# Macropad_Schematic.net
KiCad netlist of a schematic drawn in EAGLE
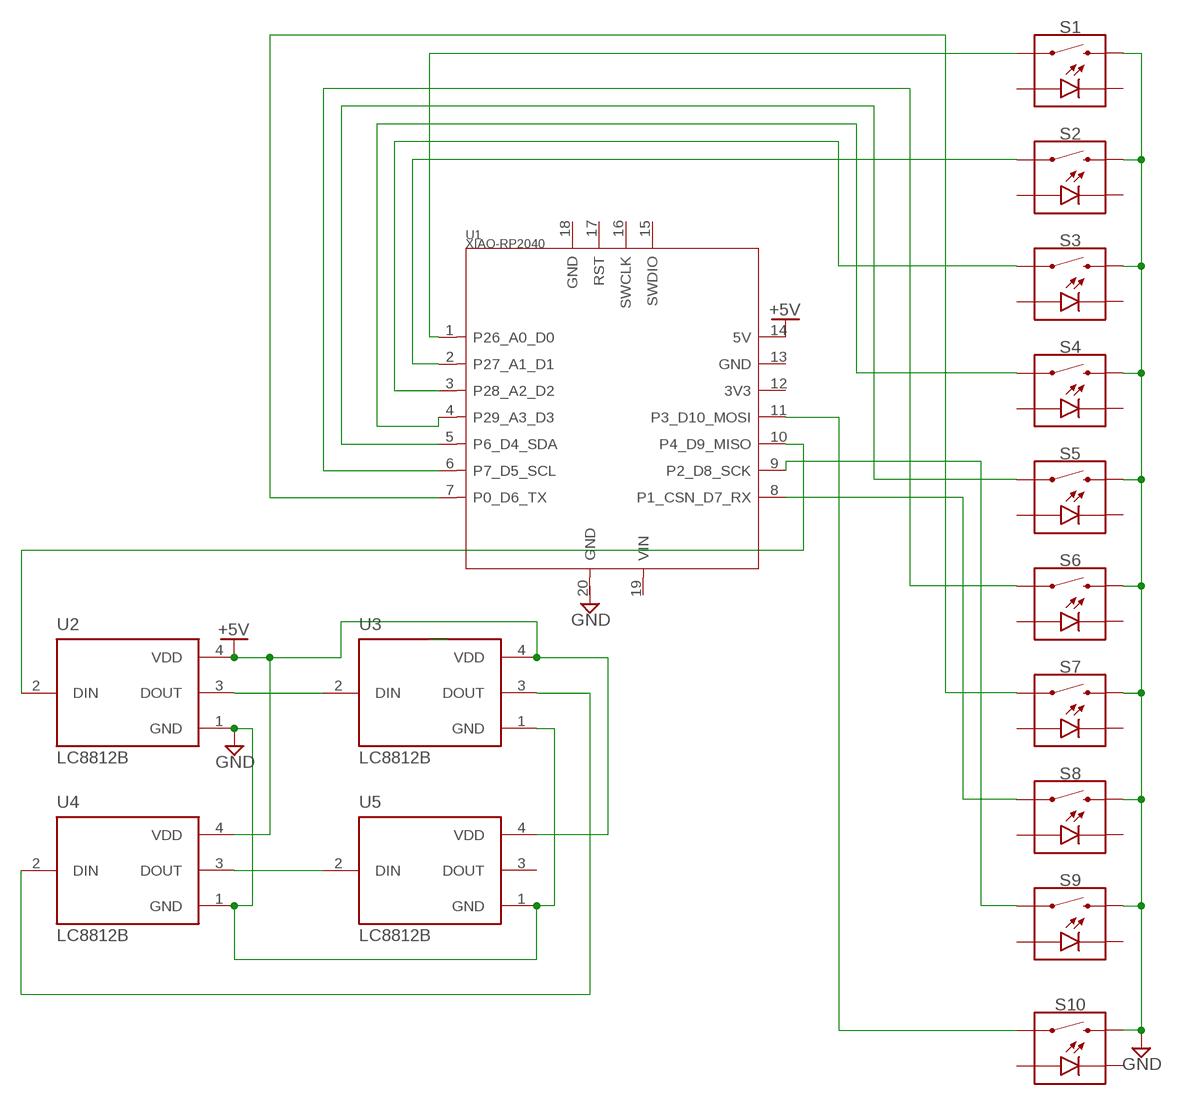
[diagram p0: schematic, sheet 1]

(export (version "E")
  (design (tool "Eeschema 10.0.6"))
  (components
    (comp (ref "S1")
      (value "MECHANICAL-KEYBOARD1U")
      (footprint "eagle-import:CHERRY-MX-LED-1U")
      (libsource (lib "eagle-import") (part "MECHANICAL-KEYBOARD1U"))
    )
    (comp (ref "S2")
      (value "MECHANICAL-KEYBOARD1U")
      (footprint "eagle-import:CHERRY-MX-LED-1U")
      (libsource (lib "eagle-import") (part "MECHANICAL-KEYBOARD1U"))
    )
    (comp (ref "S3")
      (value "MECHANICAL-KEYBOARD1U")
      (footprint "eagle-import:CHERRY-MX-LED-1U")
      (libsource (lib "eagle-import") (part "MECHANICAL-KEYBOARD1U"))
    )
    (comp (ref "S4")
      (value "MECHANICAL-KEYBOARD1U")
      (footprint "eagle-import:CHERRY-MX-LED-1U")
      (libsource (lib "eagle-import") (part "MECHANICAL-KEYBOARD1U"))
    )
    (comp (ref "S5")
      (value "MECHANICAL-KEYBOARD1U")
      (footprint "eagle-import:CHERRY-MX-LED-1U")
      (libsource (lib "eagle-import") (part "MECHANICAL-KEYBOARD1U"))
    )
    (comp (ref "S6")
      (value "MECHANICAL-KEYBOARD1U")
      (footprint "eagle-import:CHERRY-MX-LED-1U")
      (libsource (lib "eagle-import") (part "MECHANICAL-KEYBOARD1U"))
    )
    (comp (ref "S7")
      (value "MECHANICAL-KEYBOARD1U")
      (footprint "eagle-import:CHERRY-MX-LED-1U")
      (libsource (lib "eagle-import") (part "MECHANICAL-KEYBOARD1U"))
    )
    (comp (ref "S8")
      (value "MECHANICAL-KEYBOARD1U")
      (footprint "eagle-import:CHERRY-MX-LED-1U")
      (libsource (lib "eagle-import") (part "MECHANICAL-KEYBOARD1U"))
    )
    (comp (ref "S9")
      (value "MECHANICAL-KEYBOARD1U")
      (footprint "eagle-import:CHERRY-MX-LED-1U")
      (libsource (lib "eagle-import") (part "MECHANICAL-KEYBOARD1U"))
    )
    (comp (ref "S10")
      (value "MECHANICAL-KEYBOARD1U")
      (footprint "eagle-import:CHERRY-MX-LED-1U")
      (libsource (lib "eagle-import") (part "MECHANICAL-KEYBOARD1U"))
    )
    (comp (ref "U1")
      (value "XIAO-RP2040")
      (footprint "eagle-import:XIAO-SAMD21_RP2040-MODULE14P-2.54-21X17.8MM")
      (libsource (lib "eagle-import") (part "XIAO-RP2040"))
    )
    (comp (ref "U2")
      (value "LC8812B")
      (footprint "eagle-import:SOL320P540X157-4N")
      (fields (field (name "MF") "Shenzhen LED Color Optoelectronic Inc."))
      (libsource (lib "eagle-import") (part "LC8812B"))
    )
    (comp (ref "U3")
      (value "LC8812B")
      (footprint "eagle-import:SOL320P540X157-4N")
      (fields (field (name "MF") "Shenzhen LED Color Optoelectronic Inc."))
      (libsource (lib "eagle-import") (part "LC8812B"))
    )
    (comp (ref "U4")
      (value "LC8812B")
      (footprint "eagle-import:SOL320P540X157-4N")
      (fields (field (name "MF") "Shenzhen LED Color Optoelectronic Inc."))
      (libsource (lib "eagle-import") (part "LC8812B"))
    )
    (comp (ref "U5")
      (value "LC8812B")
      (footprint "eagle-import:SOL320P540X157-4N")
      (fields (field (name "MF") "Shenzhen LED Color Optoelectronic Inc."))
      (libsource (lib "eagle-import") (part "LC8812B"))
    )
  )
  (nets
    (net (code "1") (name "+5V") (class "Default")
      (node (ref "U1") (pin "14") (pinfunction "5V_14") (pintype "bidirectional"))
      (node (ref "U2") (pin "4") (pinfunction "VDD_4") (pintype "power_in"))
      (node (ref "U3") (pin "4") (pinfunction "VDD_4") (pintype "power_in"))
      (node (ref "U4") (pin "4") (pinfunction "VDD_4") (pintype "power_in"))
      (node (ref "U5") (pin "4") (pinfunction "VDD_4") (pintype "power_in"))
    )
    (net (code "2") (name "GND") (class "Default")
      (node (ref "S1") (pin "S2") (pinfunction "2_S2") (pintype "passive"))
      (node (ref "S10") (pin "S2") (pinfunction "2_S2") (pintype "passive"))
      (node (ref "S2") (pin "S2") (pinfunction "2_S2") (pintype "passive"))
      (node (ref "S3") (pin "S2") (pinfunction "2_S2") (pintype "passive"))
      (node (ref "S4") (pin "S2") (pinfunction "2_S2") (pintype "passive"))
      (node (ref "S5") (pin "S2") (pinfunction "2_S2") (pintype "passive"))
      (node (ref "S6") (pin "S2") (pinfunction "2_S2") (pintype "passive"))
      (node (ref "S7") (pin "S2") (pinfunction "2_S2") (pintype "passive"))
      (node (ref "S8") (pin "S2") (pinfunction "2_S2") (pintype "passive"))
      (node (ref "S9") (pin "S2") (pinfunction "2_S2") (pintype "passive"))
      (node (ref "U2") (pin "1") (pinfunction "GND_1") (pintype "power_in"))
      (node (ref "U3") (pin "1") (pinfunction "GND_1") (pintype "power_in"))
      (node (ref "U4") (pin "1") (pinfunction "GND_1") (pintype "power_in"))
      (node (ref "U5") (pin "1") (pinfunction "GND_1") (pintype "power_in"))
    )
    (net (code "3") (name "Net-(S1-1)") (class "Default")
      (node (ref "S1") (pin "S1") (pinfunction "1_S1") (pintype "passive"))
      (node (ref "U1") (pin "1") (pinfunction "P26_A0_D0_1") (pintype "bidirectional"))
    )
    (net (code "4") (name "Net-(S2-1)") (class "Default")
      (node (ref "S2") (pin "S1") (pinfunction "1_S1") (pintype "passive"))
      (node (ref "U1") (pin "2") (pinfunction "P27_A1_D1_2") (pintype "bidirectional"))
    )
    (net (code "5") (name "Net-(S3-1)") (class "Default")
      (node (ref "S3") (pin "S1") (pinfunction "1_S1") (pintype "passive"))
      (node (ref "U1") (pin "3") (pinfunction "P28_A2_D2_3") (pintype "bidirectional"))
    )
    (net (code "6") (name "Net-(S4-1)") (class "Default")
      (node (ref "S4") (pin "S1") (pinfunction "1_S1") (pintype "passive"))
      (node (ref "U1") (pin "4") (pinfunction "P29_A3_D3_4") (pintype "bidirectional"))
    )
    (net (code "7") (name "Net-(S5-1)") (class "Default")
      (node (ref "S5") (pin "S1") (pinfunction "1_S1") (pintype "passive"))
      (node (ref "U1") (pin "5") (pinfunction "P6_D4_SDA_5") (pintype "bidirectional"))
    )
    (net (code "8") (name "Net-(S6-1)") (class "Default")
      (node (ref "S6") (pin "S1") (pinfunction "1_S1") (pintype "passive"))
      (node (ref "U1") (pin "6") (pinfunction "P7_D5_SCL_6") (pintype "bidirectional"))
    )
    (net (code "9") (name "Net-(S7-1)") (class "Default")
      (node (ref "S7") (pin "S1") (pinfunction "1_S1") (pintype "passive"))
      (node (ref "U1") (pin "7") (pinfunction "P0_D6_TX_7") (pintype "bidirectional"))
    )
    (net (code "10") (name "Net-(S8-1)") (class "Default")
      (node (ref "S8") (pin "S1") (pinfunction "1_S1") (pintype "passive"))
      (node (ref "U1") (pin "8") (pinfunction "P1_CSN_D7_RX_8") (pintype "bidirectional"))
    )
    (net (code "11") (name "Net-(S9-1)") (class "Default")
      (node (ref "S9") (pin "S1") (pinfunction "1_S1") (pintype "passive"))
      (node (ref "U1") (pin "9") (pinfunction "P2_D8_SCK_9") (pintype "bidirectional"))
    )
    (net (code "12") (name "Net-(S10-1)") (class "Default")
      (node (ref "S10") (pin "S1") (pinfunction "1_S1") (pintype "passive"))
      (node (ref "U1") (pin "11") (pinfunction "P3_D10_MOSI_11") (pintype "bidirectional"))
    )
    (net (code "13") (name "Net-(U1-P4_D9_MISO)") (class "Default")
      (node (ref "U1") (pin "10") (pinfunction "P4_D9_MISO_10") (pintype "bidirectional"))
      (node (ref "U2") (pin "2") (pinfunction "DIN_2") (pintype "input"))
    )
    (net (code "14") (name "Net-(U2-DOUT)") (class "Default")
      (node (ref "U2") (pin "3") (pinfunction "DOUT_3") (pintype "output"))
      (node (ref "U3") (pin "2") (pinfunction "DIN_2") (pintype "input"))
    )
    (net (code "15") (name "Net-(U3-DOUT)") (class "Default")
      (node (ref "U3") (pin "3") (pinfunction "DOUT_3") (pintype "output"))
      (node (ref "U4") (pin "2") (pinfunction "DIN_2") (pintype "input"))
    )
    (net (code "16") (name "Net-(U4-DOUT)") (class "Default")
      (node (ref "U4") (pin "3") (pinfunction "DOUT_3") (pintype "output"))
      (node (ref "U5") (pin "2") (pinfunction "DIN_2") (pintype "input"))
    )
    (net (code "17") (name "unconnected-(S1-C-PadK)") (class "Default")
      (node (ref "S1") (pin "K") (pinfunction "C_K") (pintype "passive"))
    )
    (net (code "18") (name "unconnected-(S1-PadA)") (class "Default")
      (node (ref "S1") (pin "A") (pinfunction "A_A") (pintype "passive"))
    )
    (net (code "19") (name "unconnected-(S2-C-PadK)") (class "Default")
      (node (ref "S2") (pin "K") (pinfunction "C_K") (pintype "passive"))
    )
    (net (code "20") (name "unconnected-(S2-PadA)") (class "Default")
      (node (ref "S2") (pin "A") (pinfunction "A_A") (pintype "passive"))
    )
    (net (code "21") (name "unconnected-(S3-C-PadK)") (class "Default")
      (node (ref "S3") (pin "K") (pinfunction "C_K") (pintype "passive"))
    )
    (net (code "22") (name "unconnected-(S3-PadA)") (class "Default")
      (node (ref "S3") (pin "A") (pinfunction "A_A") (pintype "passive"))
    )
    (net (code "23") (name "unconnected-(S4-C-PadK)") (class "Default")
      (node (ref "S4") (pin "K") (pinfunction "C_K") (pintype "passive"))
    )
    (net (code "24") (name "unconnected-(S4-PadA)") (class "Default")
      (node (ref "S4") (pin "A") (pinfunction "A_A") (pintype "passive"))
    )
    (net (code "25") (name "unconnected-(S5-C-PadK)") (class "Default")
      (node (ref "S5") (pin "K") (pinfunction "C_K") (pintype "passive"))
    )
    (net (code "26") (name "unconnected-(S5-PadA)") (class "Default")
      (node (ref "S5") (pin "A") (pinfunction "A_A") (pintype "passive"))
    )
    (net (code "27") (name "unconnected-(S6-C-PadK)") (class "Default")
      (node (ref "S6") (pin "K") (pinfunction "C_K") (pintype "passive"))
    )
    (net (code "28") (name "unconnected-(S6-PadA)") (class "Default")
      (node (ref "S6") (pin "A") (pinfunction "A_A") (pintype "passive"))
    )
    (net (code "29") (name "unconnected-(S7-C-PadK)") (class "Default")
      (node (ref "S7") (pin "K") (pinfunction "C_K") (pintype "passive"))
    )
    (net (code "30") (name "unconnected-(S7-PadA)") (class "Default")
      (node (ref "S7") (pin "A") (pinfunction "A_A") (pintype "passive"))
    )
    (net (code "31") (name "unconnected-(S8-C-PadK)") (class "Default")
      (node (ref "S8") (pin "K") (pinfunction "C_K") (pintype "passive"))
    )
    (net (code "32") (name "unconnected-(S8-PadA)") (class "Default")
      (node (ref "S8") (pin "A") (pinfunction "A_A") (pintype "passive"))
    )
    (net (code "33") (name "unconnected-(S9-C-PadK)") (class "Default")
      (node (ref "S9") (pin "K") (pinfunction "C_K") (pintype "passive"))
    )
    (net (code "34") (name "unconnected-(S9-PadA)") (class "Default")
      (node (ref "S9") (pin "A") (pinfunction "A_A") (pintype "passive"))
    )
    (net (code "35") (name "unconnected-(S10-C-PadK)") (class "Default")
      (node (ref "S10") (pin "K") (pinfunction "C_K") (pintype "passive"))
    )
    (net (code "36") (name "unconnected-(S10-PadA)") (class "Default")
      (node (ref "S10") (pin "A") (pinfunction "A_A") (pintype "passive"))
    )
    (net (code "37") (name "unconnected-(U1-3V3-Pad12)") (class "Default")
      (node (ref "U1") (pin "12") (pinfunction "3V3_12") (pintype "bidirectional"))
    )
    (net (code "38") (name "unconnected-(U1-GND-Pad13)") (class "Default")
      (node (ref "U1") (pin "13") (pinfunction "GND_13") (pintype "bidirectional"))
    )
    (net (code "39") (name "unconnected-(U1-GND-Pad18)") (class "Default")
      (node (ref "U1") (pin "18") (pinfunction "GND_18") (pintype "bidirectional"))
    )
    (net (code "40") (name "unconnected-(U1-GND-Pad20)") (class "Default")
      (node (ref "U1") (pin "20") (pinfunction "GND_20") (pintype "bidirectional"))
    )
    (net (code "41") (name "unconnected-(U1-RST-Pad17)") (class "Default")
      (node (ref "U1") (pin "17") (pinfunction "RST_17") (pintype "bidirectional"))
    )
    (net (code "42") (name "unconnected-(U1-SWCLK-Pad16)") (class "Default")
      (node (ref "U1") (pin "16") (pinfunction "SWCLK_16") (pintype "bidirectional"))
    )
    (net (code "43") (name "unconnected-(U1-SWDIO-Pad15)") (class "Default")
      (node (ref "U1") (pin "15") (pinfunction "SWDIO_15") (pintype "bidirectional"))
    )
    (net (code "44") (name "unconnected-(U1-VIN-Pad19)") (class "Default")
      (node (ref "U1") (pin "19") (pinfunction "VIN_19") (pintype "bidirectional"))
    )
    (net (code "45") (name "unconnected-(U5-DOUT-Pad3)") (class "Default")
      (node (ref "U5") (pin "3") (pinfunction "DOUT_3") (pintype "output"))
    )
  )
)
